# ict_v361-xs.net
KiCad netlist of a schematic drawn in EAGLE
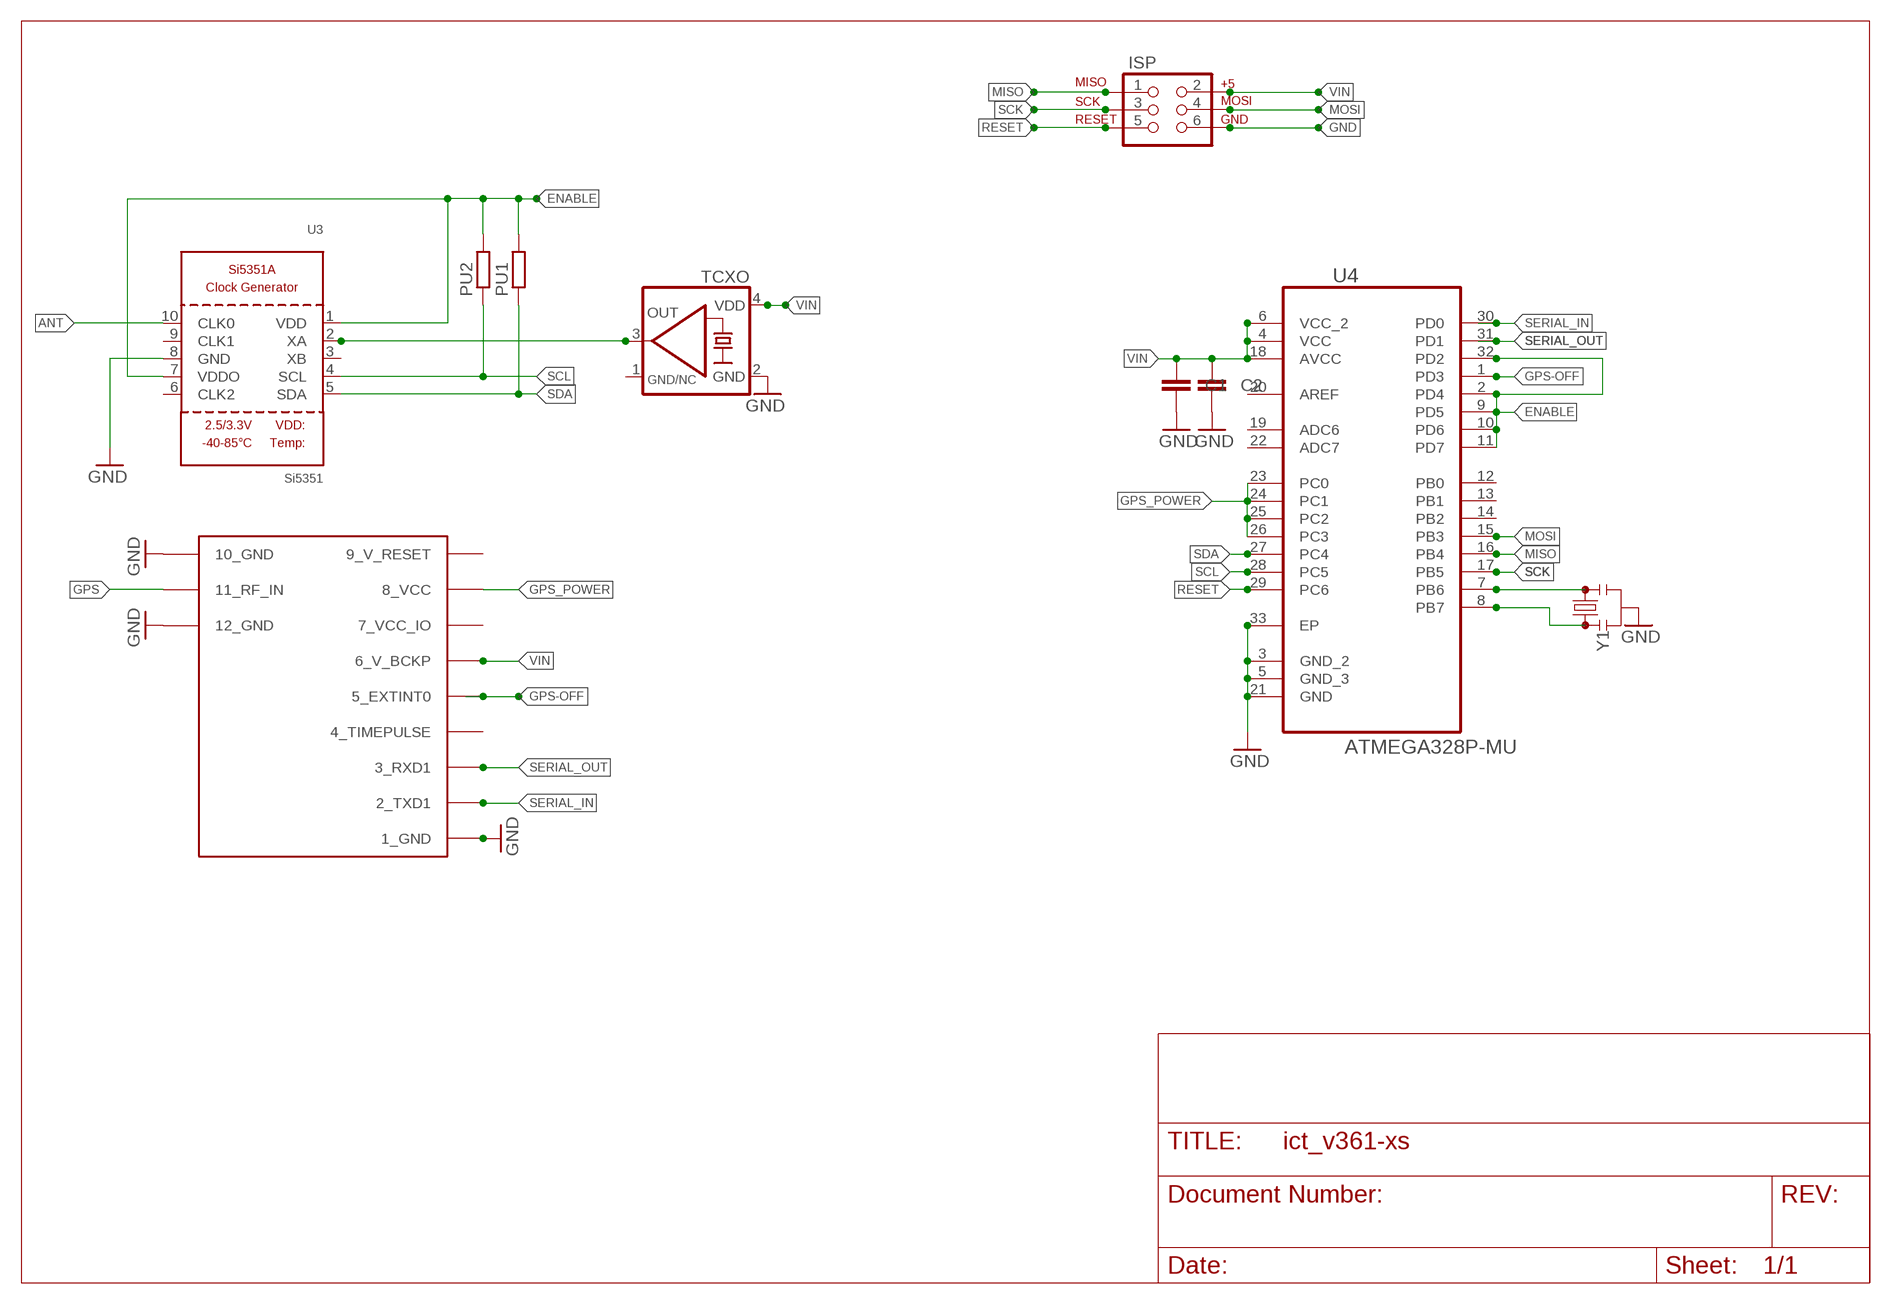
[diagram p0: schematic, sheet 1]

(export (version "E")
  (design (tool "Eeschema 10.0.6"))
  (components
    (comp (ref "C1")
      (value "C-EUC0603K")
      (footprint "eagle-import:C0603K")
      (libsource (lib "eagle-import") (part "C-EUC0603K"))
    )
    (comp (ref "C2")
      (value "C-EUC0603K")
      (footprint "eagle-import:C0603K")
      (libsource (lib "eagle-import") (part "C-EUC0603K"))
    )
    (comp (ref "ISP")
      (value "AVR_SPI_PRG_6PTH")
      (footprint "eagle-import:2X3")
      (libsource (lib "eagle-import") (part "AVR_SPI_PRG_6PTH"))
    )
    (comp (ref "PU1")
      (value "R-EU_R0603")
      (footprint "eagle-import:R0603")
      (libsource (lib "eagle-import") (part "R-EU_R0603"))
    )
    (comp (ref "PU2")
      (value "R-EU_R0603")
      (footprint "eagle-import:R0603")
      (libsource (lib "eagle-import") (part "R-EU_R0603"))
    )
    (comp (ref "TCXO")
      (value "KXO-TCXO-CMOS-84")
      (footprint "eagle-import:3.2X2.5_KXO-84-TCXO")
      (libsource (lib "eagle-import") (part "KXO-TCXO-CMOS-84"))
    )
    (comp (ref "U$2")
      (value "UBLOX_MAX")
      (footprint "eagle-import:UBLOX_MAX")
      (libsource (lib "eagle-import") (part "UBLOX_MAX"))
    )
    (comp (ref "U3")
      (value "Si5351")
      (footprint "eagle-import:MSOP10")
      (libsource (lib "eagle-import") (part "SI5351A"))
    )
    (comp (ref "U4")
      (value "ATMEGA328P-MU")
      (footprint "eagle-import:QFN50P500X500X100-33N")
      (libsource (lib "eagle-import") (part "ATMEGA328P-MU"))
    )
    (comp (ref "Y1")
      (value "RESONATORSMD-4.5X2.0")
      (footprint "eagle-import:RESONATOR-SMD-4.5X2.0")
      (libsource (lib "eagle-import") (part "RESONATORSMD-4.5X2.0"))
    )
  )
  (nets
    (net (code "1") (name "/7_VCC_IO") (class "Default")
      (node (ref "U$2") (pin "7_VCC_IO") (pinfunction "7_VCC_IO_7_VCC_IO") (pintype "power_in"))
    )
    (net (code "2") (name "/9_V_RESET") (class "Default")
      (node (ref "U$2") (pin "9_V_RESET") (pinfunction "9_V_RESET_9_V_RESET") (pintype "power_in"))
    )
    (net (code "3") (name "/GND{slash}NC") (class "Default")
      (node (ref "TCXO") (pin "1") (pinfunction "GND/NC_1") (pintype "power_in"))
    )
    (net (code "4") (name "ANT") (class "Default")
      (node (ref "U3") (pin "10") (pinfunction "CLK0_10") (pintype "output"))
    )
    (net (code "5") (name "ENABLE") (class "Default")
      (node (ref "PU1") (pin "2") (pinfunction "2_2") (pintype "passive"))
      (node (ref "PU2") (pin "2") (pinfunction "2_2") (pintype "passive"))
      (node (ref "U3") (pin "1") (pinfunction "VDD_1") (pintype "power_in"))
      (node (ref "U3") (pin "7") (pinfunction "VDDO_7") (pintype "power_in"))
      (node (ref "U4") (pin "10") (pinfunction "PD6_10") (pintype "bidirectional"))
      (node (ref "U4") (pin "11") (pinfunction "PD7_11") (pintype "bidirectional"))
      (node (ref "U4") (pin "2") (pinfunction "PD4_2") (pintype "bidirectional"))
      (node (ref "U4") (pin "32") (pinfunction "PD2_32") (pintype "bidirectional"))
      (node (ref "U4") (pin "9") (pinfunction "PD5_9") (pintype "bidirectional"))
    )
    (net (code "6") (name "GND") (class "Default")
      (node (ref "C1") (pin "2") (pinfunction "2_2") (pintype "passive"))
      (node (ref "C2") (pin "2") (pinfunction "2_2") (pintype "passive"))
      (node (ref "ISP") (pin "6") (pinfunction "6_6") (pintype "passive"))
      (node (ref "TCXO") (pin "2") (pinfunction "GND_2") (pintype "power_in"))
      (node (ref "U$2") (pin "10_GND") (pinfunction "10_GND_10_GND") (pintype "power_in"))
      (node (ref "U$2") (pin "12_GND") (pinfunction "12_GND_12_GND") (pintype "power_in"))
      (node (ref "U$2") (pin "1_GND") (pinfunction "1_GND_1_GND") (pintype "power_in"))
      (node (ref "U3") (pin "8") (pinfunction "GND_8") (pintype "power_in"))
      (node (ref "U4") (pin "21") (pinfunction "GND_21") (pintype "passive"))
      (node (ref "U4") (pin "3") (pinfunction "GND_2_3") (pintype "passive"))
      (node (ref "U4") (pin "33") (pinfunction "EP_33") (pintype "passive"))
      (node (ref "U4") (pin "5") (pinfunction "GND_3_5") (pintype "passive"))
      (node (ref "Y1") (pin "2") (pinfunction "2_2") (pintype "passive"))
    )
    (net (code "7") (name "GPS") (class "Default")
      (node (ref "U$2") (pin "11_RF_IN") (pinfunction "11_RF_IN_11_RF_IN") (pintype "bidirectional"))
    )
    (net (code "8") (name "GPS-OFF") (class "Default")
      (node (ref "U$2") (pin "5_EXTINT0") (pinfunction "5_EXTINT0_5_EXTINT0") (pintype "bidirectional"))
      (node (ref "U4") (pin "1") (pinfunction "PD3_1") (pintype "bidirectional"))
    )
    (net (code "9") (name "GPS_POWER") (class "Default")
      (node (ref "U$2") (pin "8_VCC") (pinfunction "8_VCC_8_VCC") (pintype "power_in"))
      (node (ref "U4") (pin "23") (pinfunction "PC0_23") (pintype "bidirectional"))
      (node (ref "U4") (pin "24") (pinfunction "PC1_24") (pintype "bidirectional"))
      (node (ref "U4") (pin "25") (pinfunction "PC2_25") (pintype "bidirectional"))
      (node (ref "U4") (pin "26") (pinfunction "PC3_26") (pintype "bidirectional"))
    )
    (net (code "10") (name "MISO") (class "Default")
      (node (ref "ISP") (pin "1") (pinfunction "1_1") (pintype "passive"))
      (node (ref "U4") (pin "16") (pinfunction "PB4_16") (pintype "bidirectional"))
    )
    (net (code "11") (name "MOSI") (class "Default")
      (node (ref "ISP") (pin "4") (pinfunction "4_4") (pintype "passive"))
      (node (ref "U4") (pin "15") (pinfunction "PB3_15") (pintype "bidirectional"))
    )
    (net (code "12") (name "Net-(TCXO-OUT)") (class "Default")
      (node (ref "TCXO") (pin "3") (pinfunction "OUT_3") (pintype "output"))
      (node (ref "U3") (pin "2") (pinfunction "XA_2") (pintype "input"))
    )
    (net (code "13") (name "Net-(U4-PB6)") (class "Default")
      (node (ref "U4") (pin "7") (pinfunction "PB6_7") (pintype "bidirectional"))
      (node (ref "Y1") (pin "3") (pinfunction "3_3") (pintype "passive"))
    )
    (net (code "14") (name "Net-(U4-PB7)") (class "Default")
      (node (ref "U4") (pin "8") (pinfunction "PB7_8") (pintype "bidirectional"))
      (node (ref "Y1") (pin "1") (pinfunction "1_1") (pintype "passive"))
    )
    (net (code "15") (name "RESET") (class "Default")
      (node (ref "ISP") (pin "5") (pinfunction "5_5") (pintype "passive"))
      (node (ref "U4") (pin "29") (pinfunction "PC6_29") (pintype "bidirectional"))
    )
    (net (code "16") (name "SCK") (class "Default")
      (node (ref "ISP") (pin "3") (pinfunction "3_3") (pintype "passive"))
      (node (ref "U4") (pin "17") (pinfunction "PB5_17") (pintype "bidirectional"))
    )
    (net (code "17") (name "SCL") (class "Default")
      (node (ref "PU2") (pin "1") (pinfunction "1_1") (pintype "passive"))
      (node (ref "U3") (pin "4") (pinfunction "SCL_4") (pintype "input"))
      (node (ref "U4") (pin "28") (pinfunction "PC5_28") (pintype "bidirectional"))
    )
    (net (code "18") (name "SDA") (class "Default")
      (node (ref "PU1") (pin "1") (pinfunction "1_1") (pintype "passive"))
      (node (ref "U3") (pin "5") (pinfunction "SDA_5") (pintype "bidirectional"))
      (node (ref "U4") (pin "27") (pinfunction "PC4_27") (pintype "bidirectional"))
    )
    (net (code "19") (name "SERIAL_IN") (class "Default")
      (node (ref "U$2") (pin "2_TXD1") (pinfunction "2_TXD1_2_TXD1") (pintype "bidirectional"))
      (node (ref "U4") (pin "30") (pinfunction "PD0_30") (pintype "bidirectional"))
    )
    (net (code "20") (name "SERIAL_OUT") (class "Default")
      (node (ref "U$2") (pin "3_RXD1") (pinfunction "3_RXD1_3_RXD1") (pintype "bidirectional"))
      (node (ref "U4") (pin "31") (pinfunction "PD1_31") (pintype "bidirectional"))
    )
    (net (code "21") (name "VIN") (class "Default")
      (node (ref "C1") (pin "1") (pinfunction "1_1") (pintype "passive"))
      (node (ref "C2") (pin "1") (pinfunction "1_1") (pintype "passive"))
      (node (ref "ISP") (pin "2") (pinfunction "2_2") (pintype "passive"))
      (node (ref "TCXO") (pin "4") (pinfunction "VDD_4") (pintype "power_in"))
      (node (ref "U$2") (pin "6_V_BCKP") (pinfunction "6_V_BCKP_6_V_BCKP") (pintype "bidirectional"))
      (node (ref "U4") (pin "18") (pinfunction "AVCC_18") (pintype "power_in"))
      (node (ref "U4") (pin "4") (pinfunction "VCC_4") (pintype "power_in"))
      (node (ref "U4") (pin "6") (pinfunction "VCC_2_6") (pintype "power_in"))
    )
    (net (code "22") (name "unconnected-(U$2-Pad4_TIMEPULSE)") (class "Default")
      (node (ref "U$2") (pin "4_TIMEPULSE") (pinfunction "4_TIMEPULSE_4_TIMEPULSE") (pintype "bidirectional"))
    )
    (net (code "23") (name "unconnected-(U3-CLK1-Pad9)") (class "Default")
      (node (ref "U3") (pin "9") (pinfunction "CLK1_9") (pintype "output"))
    )
    (net (code "24") (name "unconnected-(U3-CLK2-Pad6)") (class "Default")
      (node (ref "U3") (pin "6") (pinfunction "CLK2_6") (pintype "output"))
    )
    (net (code "25") (name "unconnected-(U3-XB-Pad3)") (class "Default")
      (node (ref "U3") (pin "3") (pinfunction "XB_3") (pintype "input"))
    )
    (net (code "26") (name "unconnected-(U4-ADC6-Pad19)") (class "Default")
      (node (ref "U4") (pin "19") (pinfunction "ADC6_19") (pintype "input"))
    )
    (net (code "27") (name "unconnected-(U4-ADC7-Pad22)") (class "Default")
      (node (ref "U4") (pin "22") (pinfunction "ADC7_22") (pintype "input"))
    )
    (net (code "28") (name "unconnected-(U4-AREF-Pad20)") (class "Default")
      (node (ref "U4") (pin "20") (pinfunction "AREF_20") (pintype "input"))
    )
    (net (code "29") (name "unconnected-(U4-PB0-Pad12)") (class "Default")
      (node (ref "U4") (pin "12") (pinfunction "PB0_12") (pintype "bidirectional"))
    )
    (net (code "30") (name "unconnected-(U4-PB1-Pad13)") (class "Default")
      (node (ref "U4") (pin "13") (pinfunction "PB1_13") (pintype "bidirectional"))
    )
    (net (code "31") (name "unconnected-(U4-PB2-Pad14)") (class "Default")
      (node (ref "U4") (pin "14") (pinfunction "PB2_14") (pintype "bidirectional"))
    )
  )
)
